# WLAN_Modem.net
KiCad netlist of a schematic drawn in EAGLE
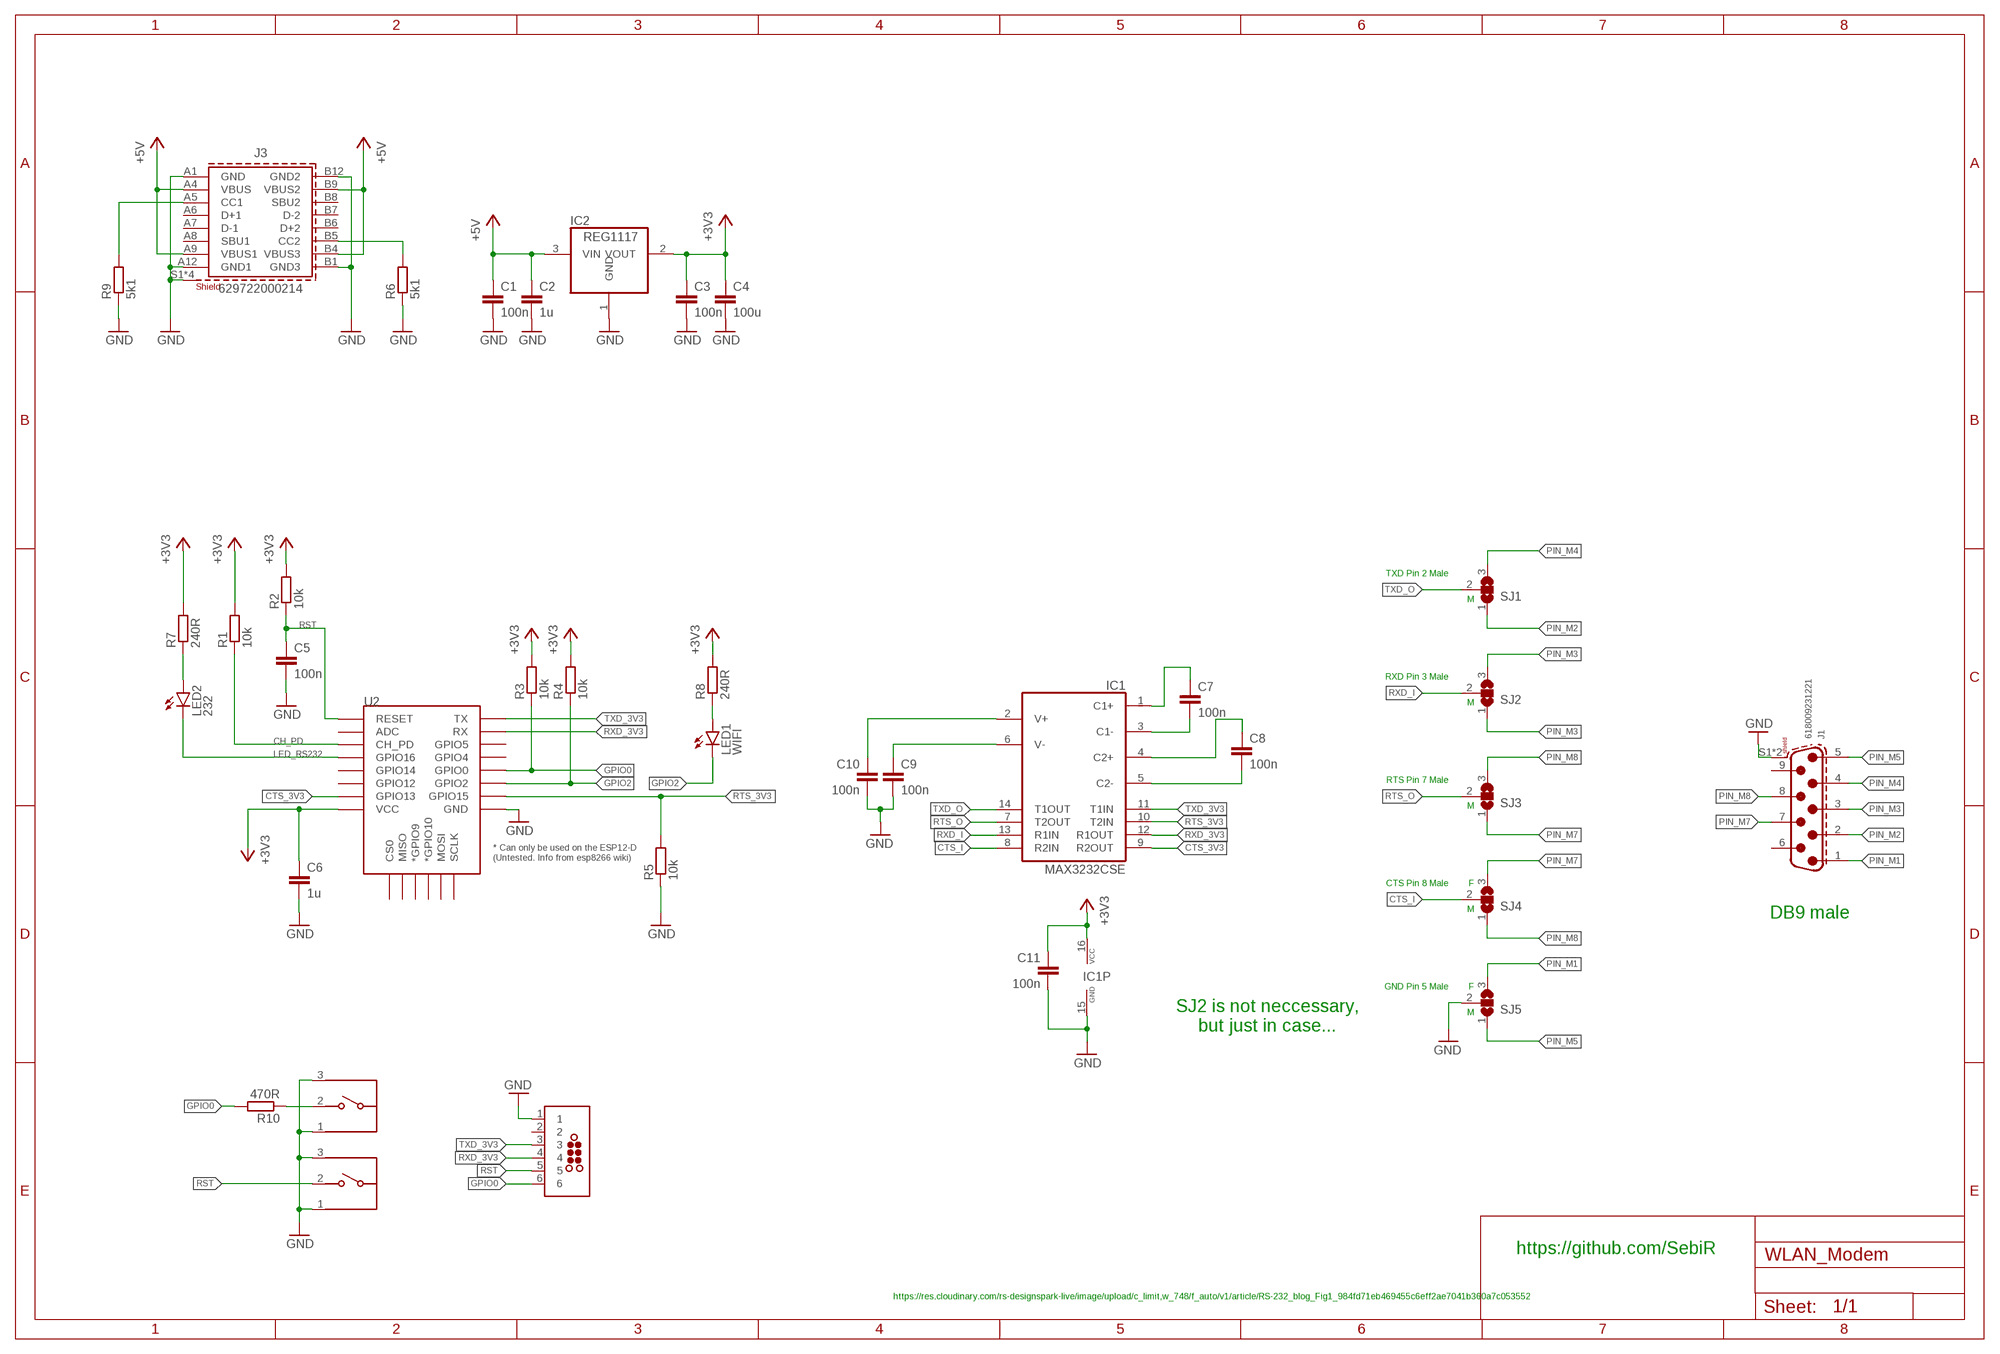
[diagram p0: schematic, sheet 1]

(export (version "E")
  (design (tool "Eeschema 10.0.6"))
  (components
    (comp (ref "C1")
      (value "100n")
      (footprint "eagle-import:C0603")
      (libsource (lib "eagle-import") (part "C-EUC0603"))
    )
    (comp (ref "C2")
      (value "1u")
      (footprint "eagle-import:C0603")
      (libsource (lib "eagle-import") (part "C-EUC0603"))
    )
    (comp (ref "C3")
      (value "100n")
      (footprint "eagle-import:C0603")
      (libsource (lib "eagle-import") (part "C-EUC0603"))
    )
    (comp (ref "C4")
      (value "100u")
      (footprint "eagle-import:C0603")
      (libsource (lib "eagle-import") (part "C-EUC0603"))
    )
    (comp (ref "C5")
      (value "100n")
      (footprint "eagle-import:C0603")
      (libsource (lib "eagle-import") (part "C-EUC0603"))
    )
    (comp (ref "C6")
      (value "1u")
      (footprint "eagle-import:C0603")
      (libsource (lib "eagle-import") (part "C-EUC0603"))
    )
    (comp (ref "C7")
      (value "100n")
      (footprint "eagle-import:C0603")
      (libsource (lib "eagle-import") (part "C-EUC0603"))
    )
    (comp (ref "C8")
      (value "100n")
      (footprint "eagle-import:C0603")
      (libsource (lib "eagle-import") (part "C-EUC0603"))
    )
    (comp (ref "C9")
      (value "100n")
      (footprint "eagle-import:C0603")
      (libsource (lib "eagle-import") (part "C-EUC0603"))
    )
    (comp (ref "C10")
      (value "100n")
      (footprint "eagle-import:C0603")
      (libsource (lib "eagle-import") (part "C-EUC0603"))
    )
    (comp (ref "C11")
      (value "100n")
      (footprint "eagle-import:C0603")
      (libsource (lib "eagle-import") (part "C-EUC0603"))
    )
    (comp (ref "IC1")
      (value "MAX3232CSE")
      (footprint "eagle-import:SO16")
      (libsource (lib "eagle-import") (part "MAX3232SEC"))
    )
    (comp (ref "IC2")
      (value "REG1117")
      (footprint "eagle-import:SOT223")
      (libsource (lib "eagle-import") (part "REG1117"))
    )
    (comp (ref "J1")
      (value "618009231221")
      (footprint "eagle-import:618009231221")
      (libsource (lib "eagle-import") (part "6180XX231221_618009231221"))
    )
    (comp (ref "J3")
      (value "629722000214")
      (footprint "eagle-import:629722000214")
      (libsource (lib "eagle-import") (part "629722000214"))
    )
    (comp (ref "J4")
      (value "TAG-CONNECT_TC2030-MCP-NL")
      (footprint "eagle-import:TAG-CONNECT_TC2030-MCP-NL")
      (libsource (lib "eagle-import") (part "TAG-CONNECT_TC2030-MCP-NL"))
    )
    (comp (ref "LED1")
      (value "WIFI")
      (footprint "eagle-import:CHIP-LED0603")
      (libsource (lib "eagle-import") (part "LEDCHIP-LED0603"))
    )
    (comp (ref "LED2")
      (value "232")
      (footprint "eagle-import:CHIP-LED0603")
      (libsource (lib "eagle-import") (part "LEDCHIP-LED0603"))
    )
    (comp (ref "R1")
      (value "10k")
      (footprint "eagle-import:R0603")
      (libsource (lib "eagle-import") (part "R-EU_R0603"))
    )
    (comp (ref "R2")
      (value "10k")
      (footprint "eagle-import:R0603")
      (libsource (lib "eagle-import") (part "R-EU_R0603"))
    )
    (comp (ref "R3")
      (value "10k")
      (footprint "eagle-import:R0603")
      (libsource (lib "eagle-import") (part "R-EU_R0603"))
    )
    (comp (ref "R4")
      (value "10k")
      (footprint "eagle-import:R0603")
      (libsource (lib "eagle-import") (part "R-EU_R0603"))
    )
    (comp (ref "R5")
      (value "10k")
      (footprint "eagle-import:R0603")
      (libsource (lib "eagle-import") (part "R-EU_R0603"))
    )
    (comp (ref "R6")
      (value "5k1")
      (footprint "eagle-import:R0603")
      (libsource (lib "eagle-import") (part "R-EU_R0603"))
    )
    (comp (ref "R7")
      (value "240R")
      (footprint "eagle-import:R0603")
      (libsource (lib "eagle-import") (part "R-EU_R0603"))
    )
    (comp (ref "R8")
      (value "240R")
      (footprint "eagle-import:R0603")
      (libsource (lib "eagle-import") (part "R-EU_R0603"))
    )
    (comp (ref "R9")
      (value "5k1")
      (footprint "eagle-import:R0603")
      (libsource (lib "eagle-import") (part "R-EU_R0603"))
    )
    (comp (ref "R10")
      (value "470R")
      (footprint "eagle-import:R0603")
      (libsource (lib "eagle-import") (part "R-EU_R0603"))
    )
    (comp (ref "S1")
      (value "436333033816")
      (footprint "eagle-import:436333033816")
      (libsource (lib "eagle-import") (part "436333033816"))
    )
    (comp (ref "S2")
      (value "436333033816")
      (footprint "eagle-import:436333033816")
      (libsource (lib "eagle-import") (part "436333033816"))
    )
    (comp (ref "SJ1")
      (value "SJ2W")
      (footprint "eagle-import:SJ_2")
      (libsource (lib "eagle-import") (part "SJ2W"))
    )
    (comp (ref "SJ2")
      (value "SJ2W")
      (footprint "eagle-import:SJ_2")
      (libsource (lib "eagle-import") (part "SJ2W"))
    )
    (comp (ref "SJ3")
      (value "SJ2W")
      (footprint "eagle-import:SJ_2")
      (libsource (lib "eagle-import") (part "SJ2W"))
    )
    (comp (ref "SJ4")
      (value "SJ2W")
      (footprint "eagle-import:SJ_2")
      (libsource (lib "eagle-import") (part "SJ2W"))
    )
    (comp (ref "SJ5")
      (value "SJ2W")
      (footprint "eagle-import:SJ_2")
      (libsource (lib "eagle-import") (part "SJ2W"))
    )
    (comp (ref "U2")
      (value "ESP12ESMD")
      (footprint "eagle-import:ESP12E-SMD")
      (libsource (lib "eagle-import") (part "ESP12ESMD"))
    )
  )
  (nets
    (net (code "1") (name "+3V3") (class "Default")
      (node (ref "C11") (pin "1") (pinfunction "1_1") (pintype "passive"))
      (node (ref "C3") (pin "1") (pinfunction "1_1") (pintype "passive"))
      (node (ref "C4") (pin "1") (pinfunction "1_1") (pintype "passive"))
      (node (ref "C6") (pin "1") (pinfunction "1_1") (pintype "passive"))
      (node (ref "IC1") (pin "16") (pinfunction "VCC_16") (pintype "power_in"))
      (node (ref "IC2") (pin "2") (pinfunction "VOUT_2") (pintype "output"))
      (node (ref "R1") (pin "2") (pinfunction "2_2") (pintype "passive"))
      (node (ref "R2") (pin "2") (pinfunction "2_2") (pintype "passive"))
      (node (ref "R3") (pin "2") (pinfunction "2_2") (pintype "passive"))
      (node (ref "R4") (pin "2") (pinfunction "2_2") (pintype "passive"))
      (node (ref "R7") (pin "2") (pinfunction "2_2") (pintype "passive"))
      (node (ref "R8") (pin "2") (pinfunction "2_2") (pintype "passive"))
      (node (ref "U2") (pin "VCC") (pinfunction "VCC_VCC") (pintype "bidirectional"))
    )
    (net (code "2") (name "+5V") (class "Default")
      (node (ref "C1") (pin "1") (pinfunction "1_1") (pintype "passive"))
      (node (ref "C2") (pin "1") (pinfunction "1_1") (pintype "passive"))
      (node (ref "IC2") (pin "3") (pinfunction "VIN_3") (pintype "input"))
      (node (ref "J3") (pin "A4") (pinfunction "VBUS_A4") (pintype "passive"))
      (node (ref "J3") (pin "A9") (pinfunction "VBUS1_A9") (pintype "passive"))
      (node (ref "J3") (pin "B4") (pinfunction "VBUS3_B4") (pintype "passive"))
      (node (ref "J3") (pin "B9") (pinfunction "VBUS2_B9") (pintype "passive"))
    )
    (net (code "3") (name "/2") (class "Default")
      (node (ref "J4") (pin "2") (pinfunction "2_2") (pintype "power_in"))
    )
    (net (code "4") (name "/CH_PD") (class "Default")
      (node (ref "R1") (pin "1") (pinfunction "1_1") (pintype "passive"))
      (node (ref "U2") (pin "CH_PD") (pinfunction "CH_PD_CH_PD") (pintype "bidirectional"))
    )
    (net (code "5") (name "/LED_RS232") (class "Default")
      (node (ref "LED2") (pin "C") (pinfunction "C_C") (pintype "passive"))
      (node (ref "U2") (pin "GPIO16") (pinfunction "GPIO16_GPIO16") (pintype "bidirectional"))
    )
    (net (code "6") (name "CTS_3V3") (class "Default")
      (node (ref "IC1") (pin "9") (pinfunction "R2OUT_9") (pintype "output"))
      (node (ref "U2") (pin "GPIO13") (pinfunction "GPIO13_GPIO13") (pintype "bidirectional"))
    )
    (net (code "7") (name "CTS_I") (class "Default")
      (node (ref "IC1") (pin "8") (pinfunction "R2IN_8") (pintype "input"))
      (node (ref "SJ4") (pin "2") (pinfunction "2_2") (pintype "passive"))
    )
    (net (code "8") (name "GND") (class "Default")
      (node (ref "C1") (pin "2") (pinfunction "2_2") (pintype "passive"))
      (node (ref "C10") (pin "2") (pinfunction "2_2") (pintype "passive"))
      (node (ref "C11") (pin "2") (pinfunction "2_2") (pintype "passive"))
      (node (ref "C2") (pin "2") (pinfunction "2_2") (pintype "passive"))
      (node (ref "C3") (pin "2") (pinfunction "2_2") (pintype "passive"))
      (node (ref "C4") (pin "2") (pinfunction "2_2") (pintype "passive"))
      (node (ref "C5") (pin "2") (pinfunction "2_2") (pintype "passive"))
      (node (ref "C6") (pin "2") (pinfunction "2_2") (pintype "passive"))
      (node (ref "C9") (pin "2") (pinfunction "2_2") (pintype "passive"))
      (node (ref "IC1") (pin "15") (pinfunction "GND_15") (pintype "power_in"))
      (node (ref "IC2") (pin "1") (pinfunction "GND_1") (pintype "power_in"))
      (node (ref "J1") (pin "S1") (pinfunction "SHIELD_S1") (pintype "bidirectional"))
      (node (ref "J1") (pin "S2") (pinfunction "SHIELD_S2") (pintype "bidirectional"))
      (node (ref "J3") (pin "A1") (pinfunction "GND_A1") (pintype "passive"))
      (node (ref "J3") (pin "A12") (pinfunction "GND1_A12") (pintype "passive"))
      (node (ref "J3") (pin "B1") (pinfunction "GND3_B1") (pintype "passive"))
      (node (ref "J3") (pin "B12") (pinfunction "GND2_B12") (pintype "passive"))
      (node (ref "J3") (pin "S1") (pinfunction "SHIELD_S1") (pintype "passive"))
      (node (ref "J3") (pin "S2") (pinfunction "SHIELD_S2") (pintype "passive"))
      (node (ref "J3") (pin "S3") (pinfunction "SHIELD_S3") (pintype "passive"))
      (node (ref "J3") (pin "S4") (pinfunction "SHIELD_S4") (pintype "passive"))
      (node (ref "J4") (pin "1") (pinfunction "1_1") (pintype "passive"))
      (node (ref "R5") (pin "1") (pinfunction "1_1") (pintype "passive"))
      (node (ref "R6") (pin "1") (pinfunction "1_1") (pintype "passive"))
      (node (ref "R9") (pin "1") (pinfunction "1_1") (pintype "passive"))
      (node (ref "S1") (pin "1") (pinfunction "1_1") (pintype "bidirectional"))
      (node (ref "S1") (pin "3") (pinfunction "3_3") (pintype "bidirectional"))
      (node (ref "S2") (pin "1") (pinfunction "1_1") (pintype "bidirectional"))
      (node (ref "S2") (pin "3") (pinfunction "3_3") (pintype "bidirectional"))
      (node (ref "SJ5") (pin "2") (pinfunction "2_2") (pintype "passive"))
      (node (ref "U2") (pin "GND") (pinfunction "GND_GND") (pintype "bidirectional"))
    )
    (net (code "9") (name "GPIO0") (class "Default")
      (node (ref "J4") (pin "6") (pinfunction "6_6") (pintype "bidirectional"))
      (node (ref "R10") (pin "2") (pinfunction "2_2") (pintype "passive"))
      (node (ref "R3") (pin "1") (pinfunction "1_1") (pintype "passive"))
      (node (ref "U2") (pin "GPIO0") (pinfunction "GPIO0_GPIO0") (pintype "bidirectional"))
    )
    (net (code "10") (name "GPIO2") (class "Default")
      (node (ref "LED1") (pin "C") (pinfunction "C_C") (pintype "passive"))
      (node (ref "R4") (pin "1") (pinfunction "1_1") (pintype "passive"))
      (node (ref "U2") (pin "GPIO2") (pinfunction "GPIO2_GPIO2") (pintype "bidirectional"))
    )
    (net (code "11") (name "Net-(IC1A-C1+)") (class "Default")
      (node (ref "C7") (pin "1") (pinfunction "1_1") (pintype "passive"))
      (node (ref "IC1") (pin "1") (pinfunction "C1+_1") (pintype "bidirectional"))
    )
    (net (code "12") (name "Net-(IC1A-C1-)") (class "Default")
      (node (ref "C7") (pin "2") (pinfunction "2_2") (pintype "passive"))
      (node (ref "IC1") (pin "3") (pinfunction "C1-_3") (pintype "bidirectional"))
    )
    (net (code "13") (name "Net-(IC1A-C2+)") (class "Default")
      (node (ref "C8") (pin "1") (pinfunction "1_1") (pintype "passive"))
      (node (ref "IC1") (pin "4") (pinfunction "C2+_4") (pintype "bidirectional"))
    )
    (net (code "14") (name "Net-(IC1A-C2-)") (class "Default")
      (node (ref "C8") (pin "2") (pinfunction "2_2") (pintype "passive"))
      (node (ref "IC1") (pin "5") (pinfunction "C2-_5") (pintype "bidirectional"))
    )
    (net (code "15") (name "Net-(IC1A-V+)") (class "Default")
      (node (ref "C10") (pin "1") (pinfunction "1_1") (pintype "passive"))
      (node (ref "IC1") (pin "2") (pinfunction "V+_2") (pintype "bidirectional"))
    )
    (net (code "16") (name "Net-(IC1A-V-)") (class "Default")
      (node (ref "C9") (pin "1") (pinfunction "1_1") (pintype "passive"))
      (node (ref "IC1") (pin "6") (pinfunction "V-_6") (pintype "bidirectional"))
    )
    (net (code "17") (name "Net-(J3-CC1)") (class "Default")
      (node (ref "J3") (pin "A5") (pinfunction "CC1_A5") (pintype "passive"))
      (node (ref "R9") (pin "2") (pinfunction "2_2") (pintype "passive"))
    )
    (net (code "18") (name "Net-(J3-CC2)") (class "Default")
      (node (ref "J3") (pin "B5") (pinfunction "CC2_B5") (pintype "passive"))
      (node (ref "R6") (pin "2") (pinfunction "2_2") (pintype "passive"))
    )
    (net (code "19") (name "Net-(LED1-PadA)") (class "Default")
      (node (ref "LED1") (pin "A") (pinfunction "A_A") (pintype "passive"))
      (node (ref "R8") (pin "1") (pinfunction "1_1") (pintype "passive"))
    )
    (net (code "20") (name "Net-(LED2-PadA)") (class "Default")
      (node (ref "LED2") (pin "A") (pinfunction "A_A") (pintype "passive"))
      (node (ref "R7") (pin "1") (pinfunction "1_1") (pintype "passive"))
    )
    (net (code "21") (name "Net-(R10-Pad1)") (class "Default")
      (node (ref "R10") (pin "1") (pinfunction "1_1") (pintype "passive"))
      (node (ref "S2") (pin "2") (pinfunction "2_2") (pintype "bidirectional"))
    )
    (net (code "22") (name "PIN_M1") (class "Default")
      (node (ref "J1") (pin "1") (pinfunction "1_1") (pintype "bidirectional"))
      (node (ref "SJ5") (pin "3") (pinfunction "3_3") (pintype "passive"))
    )
    (net (code "23") (name "PIN_M2") (class "Default")
      (node (ref "J1") (pin "2") (pinfunction "2_2") (pintype "bidirectional"))
      (node (ref "SJ1") (pin "1") (pinfunction "1_1") (pintype "passive"))
    )
    (net (code "24") (name "PIN_M3") (class "Default")
      (node (ref "J1") (pin "3") (pinfunction "3_3") (pintype "bidirectional"))
      (node (ref "SJ2") (pin "1") (pinfunction "1_1") (pintype "passive"))
      (node (ref "SJ2") (pin "3") (pinfunction "3_3") (pintype "passive"))
    )
    (net (code "25") (name "PIN_M4") (class "Default")
      (node (ref "J1") (pin "4") (pinfunction "4_4") (pintype "bidirectional"))
      (node (ref "SJ1") (pin "3") (pinfunction "3_3") (pintype "passive"))
    )
    (net (code "26") (name "PIN_M5") (class "Default")
      (node (ref "J1") (pin "5") (pinfunction "5_5") (pintype "bidirectional"))
      (node (ref "SJ5") (pin "1") (pinfunction "1_1") (pintype "passive"))
    )
    (net (code "27") (name "PIN_M7") (class "Default")
      (node (ref "J1") (pin "7") (pinfunction "7_7") (pintype "bidirectional"))
      (node (ref "SJ3") (pin "1") (pinfunction "1_1") (pintype "passive"))
      (node (ref "SJ4") (pin "3") (pinfunction "3_3") (pintype "passive"))
    )
    (net (code "28") (name "PIN_M8") (class "Default")
      (node (ref "J1") (pin "8") (pinfunction "8_8") (pintype "bidirectional"))
      (node (ref "SJ3") (pin "3") (pinfunction "3_3") (pintype "passive"))
      (node (ref "SJ4") (pin "1") (pinfunction "1_1") (pintype "passive"))
    )
    (net (code "29") (name "RST") (class "Default")
      (node (ref "C5") (pin "1") (pinfunction "1_1") (pintype "passive"))
      (node (ref "J4") (pin "5") (pinfunction "5_5") (pintype "output"))
      (node (ref "R2") (pin "1") (pinfunction "1_1") (pintype "passive"))
      (node (ref "S1") (pin "2") (pinfunction "2_2") (pintype "bidirectional"))
      (node (ref "U2") (pin "RESET") (pinfunction "RESET_RESET") (pintype "bidirectional"))
    )
    (net (code "30") (name "RTS_3V3") (class "Default")
      (node (ref "IC1") (pin "10") (pinfunction "T2IN_10") (pintype "input"))
      (node (ref "R5") (pin "2") (pinfunction "2_2") (pintype "passive"))
      (node (ref "U2") (pin "GPIO15") (pinfunction "GPIO15_GPIO15") (pintype "bidirectional"))
    )
    (net (code "31") (name "RTS_O") (class "Default")
      (node (ref "IC1") (pin "7") (pinfunction "T2OUT_7") (pintype "output"))
      (node (ref "SJ3") (pin "2") (pinfunction "2_2") (pintype "passive"))
    )
    (net (code "32") (name "RXD_3V3") (class "Default")
      (node (ref "IC1") (pin "12") (pinfunction "R1OUT_12") (pintype "output"))
      (node (ref "J4") (pin "4") (pinfunction "4_4") (pintype "bidirectional"))
      (node (ref "U2") (pin "RXD0") (pinfunction "RX_RXD0") (pintype "bidirectional"))
    )
    (net (code "33") (name "RXD_I") (class "Default")
      (node (ref "IC1") (pin "13") (pinfunction "R1IN_13") (pintype "input"))
      (node (ref "SJ2") (pin "2") (pinfunction "2_2") (pintype "passive"))
    )
    (net (code "34") (name "TXD_3V3") (class "Default")
      (node (ref "IC1") (pin "11") (pinfunction "T1IN_11") (pintype "input"))
      (node (ref "J4") (pin "3") (pinfunction "3_3") (pintype "power_in"))
      (node (ref "U2") (pin "TXD0") (pinfunction "TX_TXD0") (pintype "bidirectional"))
    )
    (net (code "35") (name "TXD_O") (class "Default")
      (node (ref "IC1") (pin "14") (pinfunction "T1OUT_14") (pintype "output"))
      (node (ref "SJ1") (pin "2") (pinfunction "2_2") (pintype "passive"))
    )
    (net (code "36") (name "unconnected-(J1-Pad6)") (class "Default")
      (node (ref "J1") (pin "6") (pinfunction "6_6") (pintype "bidirectional"))
    )
    (net (code "37") (name "unconnected-(J1-Pad9)") (class "Default")
      (node (ref "J1") (pin "9") (pinfunction "9_9") (pintype "bidirectional"))
    )
    (net (code "38") (name "unconnected-(J3-D+1-PadA6)") (class "Default")
      (node (ref "J3") (pin "A6") (pinfunction "D+1_A6") (pintype "passive"))
    )
    (net (code "39") (name "unconnected-(J3-D+2-PadB6)") (class "Default")
      (node (ref "J3") (pin "B6") (pinfunction "D+2_B6") (pintype "passive"))
    )
    (net (code "40") (name "unconnected-(J3-D-1-PadA7)") (class "Default")
      (node (ref "J3") (pin "A7") (pinfunction "D-1_A7") (pintype "passive"))
    )
    (net (code "41") (name "unconnected-(J3-D-2-PadB7)") (class "Default")
      (node (ref "J3") (pin "B7") (pinfunction "D-2_B7") (pintype "passive"))
    )
    (net (code "42") (name "unconnected-(J3-SBU1-PadA8)") (class "Default")
      (node (ref "J3") (pin "A8") (pinfunction "SBU1_A8") (pintype "passive"))
    )
    (net (code "43") (name "unconnected-(J3-SBU2-PadB8)") (class "Default")
      (node (ref "J3") (pin "B8") (pinfunction "SBU2_B8") (pintype "passive"))
    )
    (net (code "44") (name "unconnected-(U2-*GPIO9-PadGPIO9)") (class "Default")
      (node (ref "U2") (pin "GPIO9") (pinfunction "*GPIO9_GPIO9") (pintype "bidirectional"))
    )
    (net (code "45") (name "unconnected-(U2-*GPIO10-PadGPIO10)") (class "Default")
      (node (ref "U2") (pin "GPIO10") (pinfunction "*GPIO10_GPIO10") (pintype "bidirectional"))
    )
    (net (code "46") (name "unconnected-(U2-PadADC)") (class "Default")
      (node (ref "U2") (pin "ADC") (pinfunction "ADC_ADC") (pintype "bidirectional"))
    )
    (net (code "47") (name "unconnected-(U2-PadCS0)") (class "Default")
      (node (ref "U2") (pin "CS0") (pinfunction "CS0_CS0") (pintype "bidirectional"))
    )
    (net (code "48") (name "unconnected-(U2-PadGPIO4)") (class "Default")
      (node (ref "U2") (pin "GPIO4") (pinfunction "GPIO4_GPIO4") (pintype "bidirectional"))
    )
    (net (code "49") (name "unconnected-(U2-PadGPIO5)") (class "Default")
      (node (ref "U2") (pin "GPIO5") (pinfunction "GPIO5_GPIO5") (pintype "bidirectional"))
    )
    (net (code "50") (name "unconnected-(U2-PadGPIO12)") (class "Default")
      (node (ref "U2") (pin "GPIO12") (pinfunction "GPIO12_GPIO12") (pintype "bidirectional"))
    )
    (net (code "51") (name "unconnected-(U2-PadGPIO14)") (class "Default")
      (node (ref "U2") (pin "GPIO14") (pinfunction "GPIO14_GPIO14") (pintype "bidirectional"))
    )
    (net (code "52") (name "unconnected-(U2-PadMISO)") (class "Default")
      (node (ref "U2") (pin "MISO") (pinfunction "MISO_MISO") (pintype "bidirectional"))
    )
    (net (code "53") (name "unconnected-(U2-PadMOSI)") (class "Default")
      (node (ref "U2") (pin "MOSI") (pinfunction "MOSI_MOSI") (pintype "bidirectional"))
    )
    (net (code "54") (name "unconnected-(U2-PadSCLK)") (class "Default")
      (node (ref "U2") (pin "SCLK") (pinfunction "SCLK_SCLK") (pintype "bidirectional"))
    )
  )
)
